# driver_high_side.net
KiCad netlist of a schematic drawn in Altium Designer
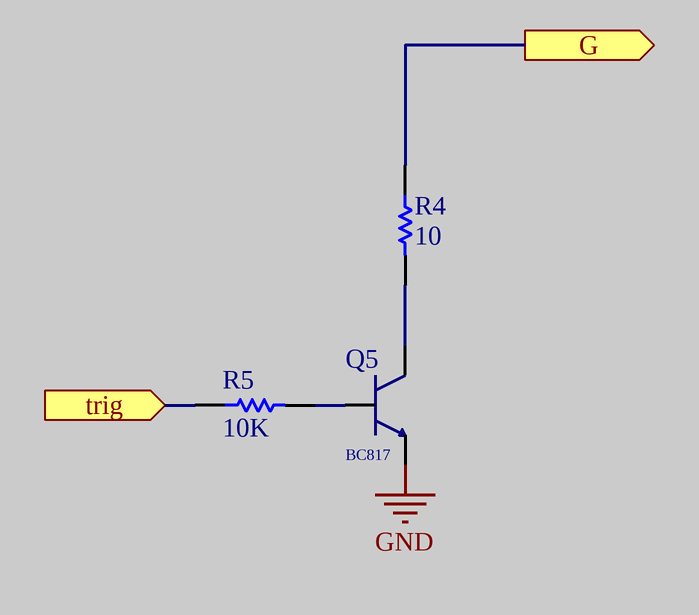
[diagram p0: driver_high_side.SchDoc]

(export (version "E")
  (design (tool "Eeschema 10.0.6"))
  (components
    (comp (ref "Q5")
      (value "NPN transistor")
      (footprint "NPN")
      (description "45 V, 0.5 A")
      (fields (field (name "TRANSISTOR") "BC817"))
      (libsource (lib "eLIB") (part "BC817"))
    )
    (comp (ref "R4")
      (value "10")
      (footprint "RESC0603")
      (description "0603,0.1W")
      (fields (field (name "PUBLISHER") "Altium Limited"))
      (libsource (lib "eLIB") (part "Resistor"))
    )
    (comp (ref "R5")
      (value "10K")
      (footprint "RESC0603")
      (description "0603,0.1W")
      (fields (field (name "PUBLISHER") "Altium Limited"))
      (libsource (lib "eLIB") (part "Resistor"))
    )
  )
  (nets
    (net (code "1") (name "/G") (class "Default")
      (node (ref "R4") (pin "1") (pinfunction "1_1") (pintype "passive"))
    )
    (net (code "2") (name "/trig") (class "Default")
      (node (ref "R5") (pin "1") (pinfunction "1_1") (pintype "passive"))
    )
    (net (code "3") (name "GND") (class "Default")
      (node (ref "Q5") (pin "2") (pinfunction "E_2") (pintype "passive"))
    )
    (net (code "4") (name "Net-(Q5-B)") (class "Default")
      (node (ref "Q5") (pin "1") (pinfunction "B_1") (pintype "passive"))
      (node (ref "R5") (pin "2") (pinfunction "2_2") (pintype "passive"))
    )
    (net (code "5") (name "Net-(Q5-C)") (class "Default")
      (node (ref "Q5") (pin "3") (pinfunction "C_3") (pintype "passive"))
      (node (ref "R4") (pin "2") (pinfunction "2_2") (pintype "passive"))
    )
  )
)
